# sb5a.net
KiCad netlist of a schematic drawn in EAGLE
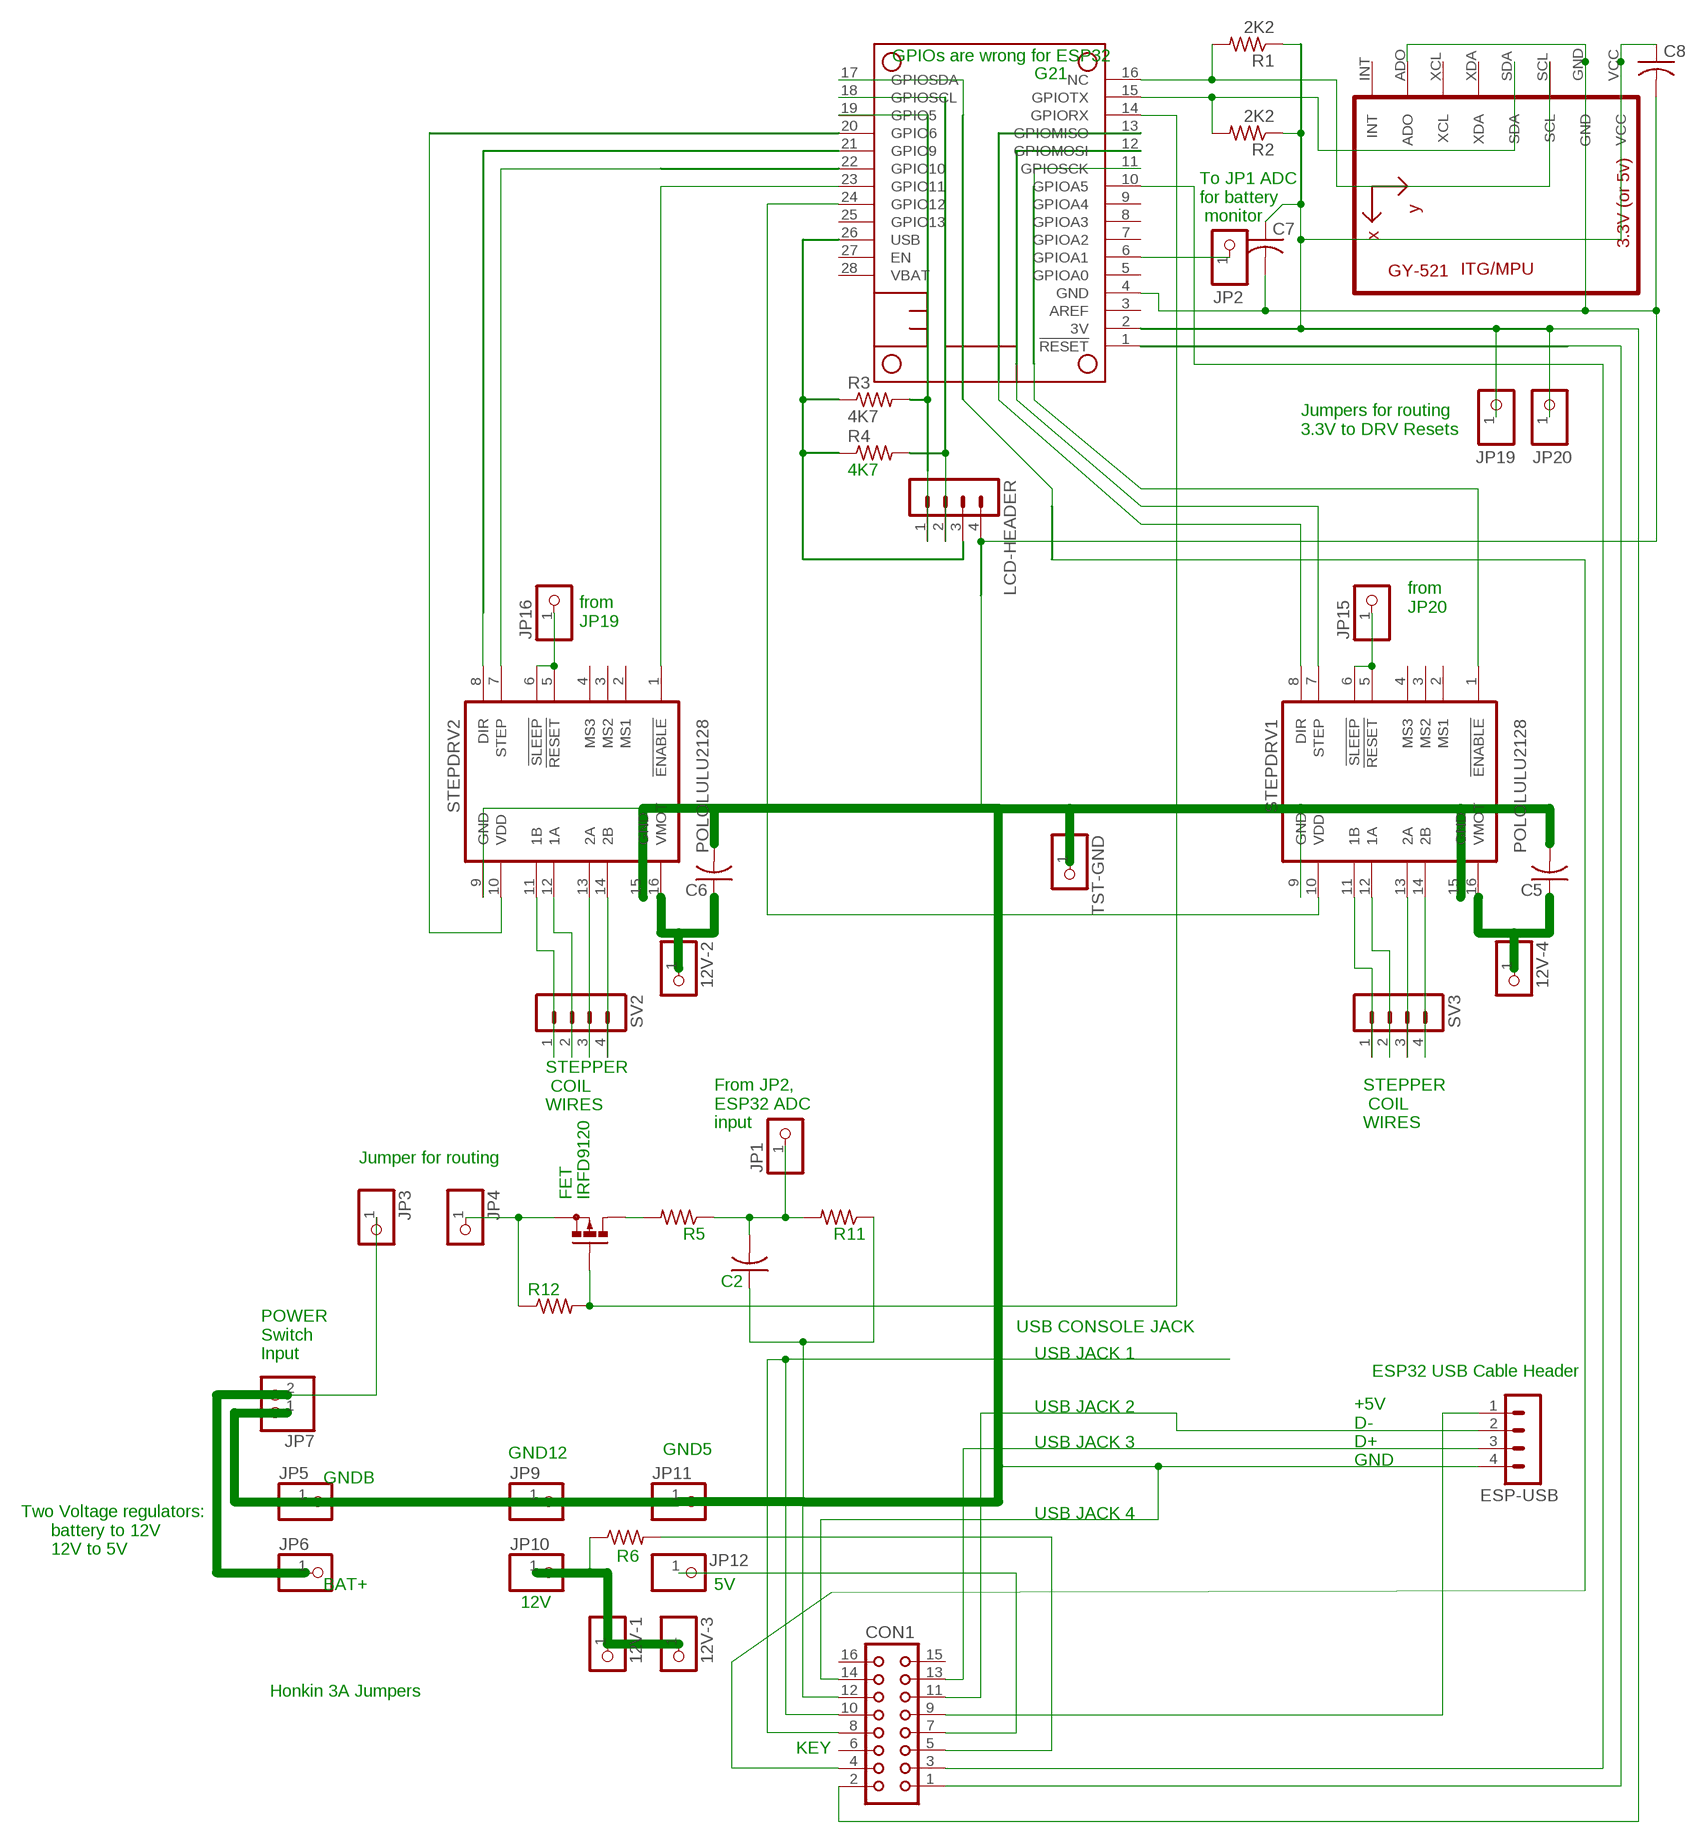
[diagram p0: schematic, sheet 1]

(export (version "E")
  (design (tool "Eeschema 10.0.6"))
  (components
    (comp (ref "12V-1")
      (value "PINHD-1X1")
      (footprint "eagle-import:1X01")
      (libsource (lib "eagle-import") (part "PINHD-1X1"))
    )
    (comp (ref "12V-2")
      (value "PINHD-1X1")
      (footprint "eagle-import:1X01")
      (libsource (lib "eagle-import") (part "PINHD-1X1"))
    )
    (comp (ref "12V-3")
      (value "PINHD-1X1")
      (footprint "eagle-import:1X01")
      (libsource (lib "eagle-import") (part "PINHD-1X1"))
    )
    (comp (ref "12V-4")
      (value "PINHD-1X1")
      (footprint "eagle-import:1X01")
      (libsource (lib "eagle-import") (part "PINHD-1X1"))
    )
    (comp (ref "C2")
      (value "C-US050-025X075")
      (footprint "eagle-import:C050-025X075")
      (libsource (lib "eagle-import") (part "C-US050-025X075"))
    )
    (comp (ref "C5")
      (value "C-US050-024X044")
      (footprint "eagle-import:C050-024X044")
      (libsource (lib "eagle-import") (part "C-US050-024X044"))
    )
    (comp (ref "C6")
      (value "C-US050-024X044")
      (footprint "eagle-import:C050-024X044")
      (libsource (lib "eagle-import") (part "C-US050-024X044"))
    )
    (comp (ref "C7")
      (value "C-US050-024X044")
      (footprint "eagle-import:C050-024X044")
      (libsource (lib "eagle-import") (part "C-US050-024X044"))
    )
    (comp (ref "C8")
      (value "C-US050-024X044")
      (footprint "eagle-import:C050-024X044")
      (libsource (lib "eagle-import") (part "C-US050-024X044"))
    )
    (comp (ref "CON1")
      (value "CON16")
      (footprint "eagle-import:CON16")
      (libsource (lib "eagle-import") (part "CON16"))
    )
    (comp (ref "ESP-USB")
      (value "MA04-1")
      (footprint "eagle-import:MA04-1")
      (libsource (lib "eagle-import") (part "MA04-1"))
    )
    (comp (ref "FET")
      (value "IRFD9120")
      (footprint "eagle-import:C370-01")
      (libsource (lib "eagle-import") (part "IRFD9120"))
    )
    (comp (ref "JP1")
      (value "PINHD-1X1")
      (footprint "eagle-import:1X01")
      (libsource (lib "eagle-import") (part "PINHD-1X1"))
    )
    (comp (ref "JP2")
      (value "PINHD-1X1")
      (footprint "eagle-import:1X01")
      (libsource (lib "eagle-import") (part "PINHD-1X1"))
    )
    (comp (ref "JP3")
      (value "PINHD-1X1")
      (footprint "eagle-import:1X01")
      (libsource (lib "eagle-import") (part "PINHD-1X1"))
    )
    (comp (ref "JP4")
      (value "PINHD-1X1")
      (footprint "eagle-import:1X01")
      (libsource (lib "eagle-import") (part "PINHD-1X1"))
    )
    (comp (ref "JP5")
      (value "PINHD-1X1")
      (footprint "eagle-import:1X01")
      (libsource (lib "eagle-import") (part "PINHD-1X1"))
    )
    (comp (ref "JP6")
      (value "PINHD-1X1")
      (footprint "eagle-import:1X01")
      (libsource (lib "eagle-import") (part "PINHD-1X1"))
    )
    (comp (ref "JP7")
      (value "PINHD-1X2")
      (footprint "eagle-import:1X02")
      (libsource (lib "eagle-import") (part "PINHD-1X2"))
    )
    (comp (ref "JP9")
      (value "PINHD-1X1")
      (footprint "eagle-import:1X01")
      (libsource (lib "eagle-import") (part "PINHD-1X1"))
    )
    (comp (ref "JP10")
      (value "PINHD-1X1")
      (footprint "eagle-import:1X01")
      (libsource (lib "eagle-import") (part "PINHD-1X1"))
    )
    (comp (ref "JP11")
      (value "PINHD-1X1")
      (footprint "eagle-import:1X01")
      (libsource (lib "eagle-import") (part "PINHD-1X1"))
    )
    (comp (ref "JP12")
      (value "PINHD-1X1")
      (footprint "eagle-import:1X01")
      (libsource (lib "eagle-import") (part "PINHD-1X1"))
    )
    (comp (ref "JP15")
      (value "PINHD-1X1")
      (footprint "eagle-import:1X01")
      (libsource (lib "eagle-import") (part "PINHD-1X1"))
    )
    (comp (ref "JP16")
      (value "PINHD-1X1")
      (footprint "eagle-import:1X01")
      (libsource (lib "eagle-import") (part "PINHD-1X1"))
    )
    (comp (ref "JP19")
      (value "PINHD-1X1")
      (footprint "eagle-import:1X01")
      (libsource (lib "eagle-import") (part "PINHD-1X1"))
    )
    (comp (ref "JP20")
      (value "PINHD-1X1")
      (footprint "eagle-import:1X01")
      (libsource (lib "eagle-import") (part "PINHD-1X1"))
    )
    (comp (ref "LCD-HEADER")
      (value "MA04-1")
      (footprint "eagle-import:MA04-1")
      (libsource (lib "eagle-import") (part "MA04-1"))
    )
    (comp (ref "MS2")
      (value "FEATHERWING_NOHOLES")
      (footprint "eagle-import:FEATHERWING_NOHOLES")
      (libsource (lib "eagle-import") (part "FEATHERWING_NOHOLES"))
    )
    (comp (ref "R1")
      (value "2K2")
      (footprint "eagle-import:0309_12")
      (libsource (lib "eagle-import") (part "resistor_348_R-US_0309/12"))
    )
    (comp (ref "R2")
      (value "2K2")
      (footprint "eagle-import:0309_12")
      (libsource (lib "eagle-import") (part "resistor_348_R-US_0309/12"))
    )
    (comp (ref "R3")
      (value "4K7")
      (footprint "eagle-import:0309_12")
      (libsource (lib "eagle-import") (part "resistor_348_R-US_0309/12"))
    )
    (comp (ref "R4")
      (value "4K7")
      (footprint "eagle-import:0309_12")
      (libsource (lib "eagle-import") (part "resistor_348_R-US_0309/12"))
    )
    (comp (ref "R5")
      (value "R-US_0207/10")
      (footprint "eagle-import:0207_10")
      (libsource (lib "eagle-import") (part "R-US_0207/10"))
    )
    (comp (ref "R6")
      (value "R-US_0207/10")
      (footprint "eagle-import:0207_10")
      (libsource (lib "eagle-import") (part "R-US_0207/10"))
    )
    (comp (ref "R11")
      (value "R-US_0207/10")
      (footprint "eagle-import:0207_10")
      (libsource (lib "eagle-import") (part "R-US_0207/10"))
    )
    (comp (ref "R12")
      (value "R-US_0207/10")
      (footprint "eagle-import:0207_10")
      (libsource (lib "eagle-import") (part "R-US_0207/10"))
    )
    (comp (ref "STEPDRV1")
      (value "POLOLULU2128")
      (footprint "eagle-import:POLOLULU2128")
      (libsource (lib "eagle-import") (part "POLOLULU2128"))
    )
    (comp (ref "STEPDRV2")
      (value "POLOLULU2128")
      (footprint "eagle-import:POLOLULU2128")
      (libsource (lib "eagle-import") (part "POLOLULU2128"))
    )
    (comp (ref "SV2")
      (value "MA04-1")
      (footprint "eagle-import:MA04-1")
      (libsource (lib "eagle-import") (part "MA04-1"))
    )
    (comp (ref "SV3")
      (value "MA04-1")
      (footprint "eagle-import:MA04-1")
      (libsource (lib "eagle-import") (part "MA04-1"))
    )
    (comp (ref "TST-GND")
      (value "PINHD-1X1")
      (footprint "eagle-import:1X01")
      (libsource (lib "eagle-import") (part "PINHD-1X1"))
    )
    (comp (ref "U1")
      (value "GY-521MPU6050")
      (footprint "eagle-import:GY-521")
      (libsource (lib "eagle-import") (part "GY-521MPU6050"))
    )
  )
  (nets
    (net (code "1") (name "/VBAT") (class "Default")
      (node (ref "MS2") (pin "28") (pinfunction "VBAT_28") (pintype "power_in"))
    )
    (net (code "2") (name "Net-(12V-1-Pad1)") (class "Default")
      (node (ref "12V-1") (pin "1") (pinfunction "1_1") (pintype "passive"))
      (node (ref "12V-3") (pin "1") (pinfunction "1_1") (pintype "passive"))
      (node (ref "JP10") (pin "1") (pinfunction "1_1") (pintype "passive"))
      (node (ref "R6") (pin "1") (pinfunction "1_1") (pintype "passive"))
    )
    (net (code "3") (name "Net-(C2-Pad2)") (class "Default")
      (node (ref "C2") (pin "2") (pinfunction "2_2") (pintype "passive"))
      (node (ref "JP1") (pin "1") (pinfunction "1_1") (pintype "passive"))
      (node (ref "R11") (pin "2") (pinfunction "2_2") (pintype "passive"))
      (node (ref "R5") (pin "1") (pinfunction "1_1") (pintype "passive"))
    )
    (net (code "4") (name "Net-(CON1-Pad5)") (class "Default")
      (node (ref "CON1") (pin "5") (pinfunction "5_5") (pintype "passive"))
      (node (ref "R6") (pin "2") (pinfunction "2_2") (pintype "passive"))
    )
    (net (code "5") (name "Net-(CON1-Pad7)") (class "Default")
      (node (ref "CON1") (pin "7") (pinfunction "7_7") (pintype "passive"))
      (node (ref "JP12") (pin "1") (pinfunction "1_1") (pintype "passive"))
    )
    (net (code "6") (name "Net-(CON1-Pad9)") (class "Default")
      (node (ref "CON1") (pin "9") (pinfunction "9_9") (pintype "passive"))
      (node (ref "ESP-USB") (pin "1") (pinfunction "1_1") (pintype "passive"))
    )
    (net (code "7") (name "Net-(CON1-Pad10)") (class "Default")
      (node (ref "CON1") (pin "10") (pinfunction "10_10") (pintype "passive"))
      (node (ref "CON1") (pin "8") (pinfunction "8_8") (pintype "passive"))
    )
    (net (code "8") (name "Net-(CON1-Pad11)") (class "Default")
      (node (ref "CON1") (pin "11") (pinfunction "11_11") (pintype "passive"))
      (node (ref "ESP-USB") (pin "2") (pinfunction "2_2") (pintype "passive"))
    )
    (net (code "9") (name "Net-(CON1-Pad13)") (class "Default")
      (node (ref "CON1") (pin "13") (pinfunction "13_13") (pintype "passive"))
      (node (ref "ESP-USB") (pin "3") (pinfunction "3_3") (pintype "passive"))
    )
    (net (code "10") (name "Net-(FET-D-PadD1)") (class "Default")
      (node (ref "FET") (pin "D") (pinfunction "D_D") (pintype "passive"))
      (node (ref "FET") (pin "D1") (pinfunction "D_D1") (pintype "passive"))
      (node (ref "R5") (pin "2") (pinfunction "2_2") (pintype "passive"))
    )
    (net (code "11") (name "Net-(FET-PadS)") (class "Default")
      (node (ref "FET") (pin "S") (pinfunction "S_S") (pintype "passive"))
      (node (ref "JP4") (pin "1") (pinfunction "1_1") (pintype "passive"))
      (node (ref "R12") (pin "1") (pinfunction "1_1") (pintype "passive"))
    )
    (net (code "12") (name "Net-(JP3-Pad1)") (class "Default")
      (node (ref "JP3") (pin "1") (pinfunction "1_1") (pintype "passive"))
      (node (ref "JP6") (pin "1") (pinfunction "1_1") (pintype "passive"))
      (node (ref "JP7") (pin "2") (pinfunction "2_2") (pintype "passive"))
    )
    (net (code "13") (name "Net-(MS2-3V)") (class "Default")
      (node (ref "C7") (pin "1") (pinfunction "1_1") (pintype "passive"))
      (node (ref "C8") (pin "1") (pinfunction "1_1") (pintype "passive"))
      (node (ref "CON1") (pin "2") (pinfunction "2_2") (pintype "passive"))
      (node (ref "JP19") (pin "1") (pinfunction "1_1") (pintype "passive"))
      (node (ref "JP20") (pin "1") (pinfunction "1_1") (pintype "passive"))
      (node (ref "MS2") (pin "2") (pinfunction "3V_2") (pintype "power_in"))
      (node (ref "R1") (pin "1") (pinfunction "1_1") (pintype "passive"))
      (node (ref "R2") (pin "1") (pinfunction "1_1") (pintype "passive"))
      (node (ref "U1") (pin "VCC") (pinfunction "VCC_VCC") (pintype "bidirectional"))
    )
    (net (code "14") (name "Net-(MS2-GND)") (class "Default")
      (node (ref "C2") (pin "1") (pinfunction "1_1") (pintype "passive"))
      (node (ref "C5") (pin "2") (pinfunction "2_2") (pintype "passive"))
      (node (ref "C6") (pin "2") (pinfunction "2_2") (pintype "passive"))
      (node (ref "C7") (pin "2") (pinfunction "2_2") (pintype "passive"))
      (node (ref "C8") (pin "2") (pinfunction "2_2") (pintype "passive"))
      (node (ref "CON1") (pin "12") (pinfunction "12_12") (pintype "passive"))
      (node (ref "CON1") (pin "14") (pinfunction "14_14") (pintype "passive"))
      (node (ref "ESP-USB") (pin "4") (pinfunction "4_4") (pintype "passive"))
      (node (ref "JP11") (pin "1") (pinfunction "1_1") (pintype "passive"))
      (node (ref "JP5") (pin "1") (pinfunction "1_1") (pintype "passive"))
      (node (ref "JP7") (pin "1") (pinfunction "1_1") (pintype "passive"))
      (node (ref "JP9") (pin "1") (pinfunction "1_1") (pintype "passive"))
      (node (ref "LCD-HEADER") (pin "4") (pinfunction "4_4") (pintype "passive"))
      (node (ref "MS2") (pin "4") (pinfunction "GND_4") (pintype "power_in"))
      (node (ref "R11") (pin "1") (pinfunction "1_1") (pintype "passive"))
      (node (ref "STEPDRV1") (pin "15") (pinfunction "GND_15") (pintype "power_in"))
      (node (ref "STEPDRV1") (pin "9") (pinfunction "GND_9") (pintype "power_in"))
      (node (ref "STEPDRV2") (pin "15") (pinfunction "GND_15") (pintype "power_in"))
      (node (ref "STEPDRV2") (pin "9") (pinfunction "GND_9") (pintype "power_in"))
      (node (ref "TST-GND") (pin "1") (pinfunction "1_1") (pintype "passive"))
      (node (ref "U1") (pin "ADO") (pinfunction "ADO_ADO") (pintype "bidirectional"))
      (node (ref "U1") (pin "GND") (pinfunction "GND_GND") (pintype "bidirectional"))
    )
    (net (code "15") (name "Net-(MS2-GPIO5)") (class "Default")
      (node (ref "LCD-HEADER") (pin "1") (pinfunction "1_1") (pintype "passive"))
      (node (ref "MS2") (pin "19") (pinfunction "GPIO5_19") (pintype "bidirectional"))
      (node (ref "R3") (pin "2") (pinfunction "2_2") (pintype "passive"))
    )
    (net (code "16") (name "Net-(MS2-GPIO6)") (class "Default")
      (node (ref "MS2") (pin "20") (pinfunction "GPIO6_20") (pintype "bidirectional"))
      (node (ref "STEPDRV2") (pin "10") (pinfunction "VDD_10") (pintype "power_in"))
    )
    (net (code "17") (name "Net-(MS2-GPIO9)") (class "Default")
      (node (ref "MS2") (pin "21") (pinfunction "GPIO9_21") (pintype "bidirectional"))
      (node (ref "STEPDRV2") (pin "8") (pinfunction "DIR_8") (pintype "input"))
    )
    (net (code "18") (name "Net-(MS2-GPIO10)") (class "Default")
      (node (ref "MS2") (pin "22") (pinfunction "GPIO10_22") (pintype "bidirectional"))
      (node (ref "STEPDRV2") (pin "7") (pinfunction "STEP_7") (pintype "input"))
    )
    (net (code "19") (name "Net-(MS2-GPIO11)") (class "Default")
      (node (ref "MS2") (pin "23") (pinfunction "GPIO11_23") (pintype "bidirectional"))
      (node (ref "STEPDRV2") (pin "1") (pinfunction "~{ENABLE}_1") (pintype "input"))
    )
    (net (code "20") (name "Net-(MS2-GPIO12)") (class "Default")
      (node (ref "MS2") (pin "24") (pinfunction "GPIO12_24") (pintype "bidirectional"))
      (node (ref "STEPDRV1") (pin "10") (pinfunction "VDD_10") (pintype "power_in"))
    )
    (net (code "21") (name "Net-(MS2-GPIOA1)") (class "Default")
      (node (ref "JP2") (pin "1") (pinfunction "1_1") (pintype "passive"))
      (node (ref "MS2") (pin "6") (pinfunction "GPIOA1_6") (pintype "bidirectional"))
    )
    (net (code "22") (name "Net-(MS2-GPIOA5)") (class "Default")
      (node (ref "CON1") (pin "3") (pinfunction "3_3") (pintype "passive"))
      (node (ref "MS2") (pin "10") (pinfunction "GPIOA5_10") (pintype "bidirectional"))
    )
    (net (code "23") (name "Net-(MS2-GPIOMISO)") (class "Default")
      (node (ref "MS2") (pin "13") (pinfunction "GPIOMISO_13") (pintype "bidirectional"))
      (node (ref "STEPDRV1") (pin "8") (pinfunction "DIR_8") (pintype "input"))
    )
    (net (code "24") (name "Net-(MS2-GPIOMOSI)") (class "Default")
      (node (ref "MS2") (pin "12") (pinfunction "GPIOMOSI_12") (pintype "bidirectional"))
      (node (ref "STEPDRV1") (pin "7") (pinfunction "STEP_7") (pintype "input"))
    )
    (net (code "25") (name "Net-(MS2-GPIORX)") (class "Default")
      (node (ref "FET") (pin "G") (pinfunction "G_G") (pintype "passive"))
      (node (ref "MS2") (pin "14") (pinfunction "GPIORX_14") (pintype "bidirectional"))
      (node (ref "R12") (pin "2") (pinfunction "2_2") (pintype "passive"))
    )
    (net (code "26") (name "Net-(MS2-GPIOSCK)") (class "Default")
      (node (ref "MS2") (pin "11") (pinfunction "GPIOSCK_11") (pintype "bidirectional"))
      (node (ref "STEPDRV1") (pin "1") (pinfunction "~{ENABLE}_1") (pintype "input"))
    )
    (net (code "27") (name "Net-(MS2-GPIOSCL)") (class "Default")
      (node (ref "LCD-HEADER") (pin "2") (pinfunction "2_2") (pintype "passive"))
      (node (ref "MS2") (pin "18") (pinfunction "GPIOSCL_18") (pintype "bidirectional"))
      (node (ref "R4") (pin "2") (pinfunction "2_2") (pintype "passive"))
    )
    (net (code "28") (name "Net-(MS2-GPIOSDA)") (class "Default")
      (node (ref "CON1") (pin "4") (pinfunction "4_4") (pintype "passive"))
      (node (ref "MS2") (pin "17") (pinfunction "GPIOSDA_17") (pintype "bidirectional"))
    )
    (net (code "29") (name "Net-(MS2-GPIOTX)") (class "Default")
      (node (ref "MS2") (pin "15") (pinfunction "GPIOTX_15") (pintype "bidirectional"))
      (node (ref "R2") (pin "2") (pinfunction "2_2") (pintype "passive"))
      (node (ref "U1") (pin "SDA") (pinfunction "SDA_SDA") (pintype "bidirectional"))
    )
    (net (code "30") (name "Net-(MS2-NC)") (class "Default")
      (node (ref "MS2") (pin "16") (pinfunction "NC_16") (pintype "passive"))
      (node (ref "R1") (pin "2") (pinfunction "2_2") (pintype "passive"))
      (node (ref "U1") (pin "SCL") (pinfunction "SCL_SCL") (pintype "bidirectional"))
    )
    (net (code "31") (name "Net-(MS2-USB)") (class "Default")
      (node (ref "LCD-HEADER") (pin "3") (pinfunction "3_3") (pintype "passive"))
      (node (ref "MS2") (pin "26") (pinfunction "USB_26") (pintype "power_in"))
      (node (ref "R3") (pin "1") (pinfunction "1_1") (pintype "passive"))
      (node (ref "R4") (pin "1") (pinfunction "1_1") (pintype "passive"))
    )
    (net (code "32") (name "Net-(MS2-~{RESET})") (class "Default")
      (node (ref "CON1") (pin "1") (pinfunction "1_1") (pintype "passive"))
      (node (ref "MS2") (pin "1") (pinfunction "~{RESET}_1") (pintype "input"))
    )
    (net (code "33") (name "Net-(STEPDRV1-1A)") (class "Default")
      (node (ref "STEPDRV1") (pin "12") (pinfunction "1A_12") (pintype "output"))
      (node (ref "SV3") (pin "2") (pinfunction "2_2") (pintype "passive"))
    )
    (net (code "34") (name "Net-(STEPDRV1-1B)") (class "Default")
      (node (ref "STEPDRV1") (pin "11") (pinfunction "1B_11") (pintype "output"))
      (node (ref "SV3") (pin "1") (pinfunction "1_1") (pintype "passive"))
    )
    (net (code "35") (name "Net-(STEPDRV1-2A)") (class "Default")
      (node (ref "STEPDRV1") (pin "13") (pinfunction "2A_13") (pintype "output"))
      (node (ref "SV3") (pin "3") (pinfunction "3_3") (pintype "passive"))
    )
    (net (code "36") (name "Net-(STEPDRV1-2B)") (class "Default")
      (node (ref "STEPDRV1") (pin "14") (pinfunction "2B_14") (pintype "output"))
      (node (ref "SV3") (pin "4") (pinfunction "4_4") (pintype "passive"))
    )
    (net (code "37") (name "Net-(STEPDRV1-VMOT)") (class "Default")
      (node (ref "12V-4") (pin "1") (pinfunction "1_1") (pintype "passive"))
      (node (ref "C5") (pin "1") (pinfunction "1_1") (pintype "passive"))
      (node (ref "STEPDRV1") (pin "16") (pinfunction "VMOT_16") (pintype "power_in"))
    )
    (net (code "38") (name "Net-(STEPDRV1-~{RESET})") (class "Default")
      (node (ref "JP15") (pin "1") (pinfunction "1_1") (pintype "passive"))
      (node (ref "STEPDRV1") (pin "5") (pinfunction "~{RESET}_5") (pintype "input"))
      (node (ref "STEPDRV1") (pin "6") (pinfunction "~{SLEEP}_6") (pintype "input"))
    )
    (net (code "39") (name "Net-(STEPDRV2-1A)") (class "Default")
      (node (ref "STEPDRV2") (pin "12") (pinfunction "1A_12") (pintype "output"))
      (node (ref "SV2") (pin "2") (pinfunction "2_2") (pintype "passive"))
    )
    (net (code "40") (name "Net-(STEPDRV2-1B)") (class "Default")
      (node (ref "STEPDRV2") (pin "11") (pinfunction "1B_11") (pintype "output"))
      (node (ref "SV2") (pin "1") (pinfunction "1_1") (pintype "passive"))
    )
    (net (code "41") (name "Net-(STEPDRV2-2A)") (class "Default")
      (node (ref "STEPDRV2") (pin "13") (pinfunction "2A_13") (pintype "output"))
      (node (ref "SV2") (pin "3") (pinfunction "3_3") (pintype "passive"))
    )
    (net (code "42") (name "Net-(STEPDRV2-2B)") (class "Default")
      (node (ref "STEPDRV2") (pin "14") (pinfunction "2B_14") (pintype "output"))
      (node (ref "SV2") (pin "4") (pinfunction "4_4") (pintype "passive"))
    )
    (net (code "43") (name "Net-(STEPDRV2-VMOT)") (class "Default")
      (node (ref "12V-2") (pin "1") (pinfunction "1_1") (pintype "passive"))
      (node (ref "C6") (pin "1") (pinfunction "1_1") (pintype "passive"))
      (node (ref "STEPDRV2") (pin "16") (pinfunction "VMOT_16") (pintype "power_in"))
    )
    (net (code "44") (name "Net-(STEPDRV2-~{RESET})") (class "Default")
      (node (ref "JP16") (pin "1") (pinfunction "1_1") (pintype "passive"))
      (node (ref "STEPDRV2") (pin "5") (pinfunction "~{RESET}_5") (pintype "input"))
      (node (ref "STEPDRV2") (pin "6") (pinfunction "~{SLEEP}_6") (pintype "input"))
    )
    (net (code "45") (name "unconnected-(CON1-Pad6)") (class "Default")
      (node (ref "CON1") (pin "6") (pinfunction "6_6") (pintype "passive"))
    )
    (net (code "46") (name "unconnected-(CON1-Pad15)") (class "Default")
      (node (ref "CON1") (pin "15") (pinfunction "15_15") (pintype "passive"))
    )
    (net (code "47") (name "unconnected-(CON1-Pad16)") (class "Default")
      (node (ref "CON1") (pin "16") (pinfunction "16_16") (pintype "passive"))
    )
    (net (code "48") (name "unconnected-(MS2-AREF-Pad3)") (class "Default")
      (node (ref "MS2") (pin "3") (pinfunction "AREF_3") (pintype "passive"))
    )
    (net (code "49") (name "unconnected-(MS2-EN-Pad27)") (class "Default")
      (node (ref "MS2") (pin "27") (pinfunction "EN_27") (pintype "passive"))
    )
    (net (code "50") (name "unconnected-(MS2-GPIO13-Pad25)") (class "Default")
      (node (ref "MS2") (pin "25") (pinfunction "GPIO13_25") (pintype "bidirectional"))
    )
    (net (code "51") (name "unconnected-(MS2-GPIOA0-Pad5)") (class "Default")
      (node (ref "MS2") (pin "5") (pinfunction "GPIOA0_5") (pintype "bidirectional"))
    )
    (net (code "52") (name "unconnected-(MS2-GPIOA2-Pad7)") (class "Default")
      (node (ref "MS2") (pin "7") (pinfunction "GPIOA2_7") (pintype "bidirectional"))
    )
    (net (code "53") (name "unconnected-(MS2-GPIOA3-Pad8)") (class "Default")
      (node (ref "MS2") (pin "8") (pinfunction "GPIOA3_8") (pintype "bidirectional"))
    )
    (net (code "54") (name "unconnected-(MS2-GPIOA4-Pad9)") (class "Default")
      (node (ref "MS2") (pin "9") (pinfunction "GPIOA4_9") (pintype "bidirectional"))
    )
    (net (code "55") (name "unconnected-(STEPDRV1-MS1-Pad2)") (class "Default")
      (node (ref "STEPDRV1") (pin "2") (pinfunction "MS1_2") (pintype "input"))
    )
    (net (code "56") (name "unconnected-(STEPDRV1-MS2-Pad3)") (class "Default")
      (node (ref "STEPDRV1") (pin "3") (pinfunction "MS2_3") (pintype "input"))
    )
    (net (code "57") (name "unconnected-(STEPDRV1-MS3-Pad4)") (class "Default")
      (node (ref "STEPDRV1") (pin "4") (pinfunction "MS3_4") (pintype "input"))
    )
    (net (code "58") (name "unconnected-(STEPDRV2-MS1-Pad2)") (class "Default")
      (node (ref "STEPDRV2") (pin "2") (pinfunction "MS1_2") (pintype "input"))
    )
    (net (code "59") (name "unconnected-(STEPDRV2-MS2-Pad3)") (class "Default")
      (node (ref "STEPDRV2") (pin "3") (pinfunction "MS2_3") (pintype "input"))
    )
    (net (code "60") (name "unconnected-(STEPDRV2-MS3-Pad4)") (class "Default")
      (node (ref "STEPDRV2") (pin "4") (pinfunction "MS3_4") (pintype "input"))
    )
    (net (code "61") (name "unconnected-(U1-PadINT)") (class "Default")
      (node (ref "U1") (pin "INT") (pinfunction "INT_INT") (pintype "bidirectional"))
    )
    (net (code "62") (name "unconnected-(U1-PadXCL)") (class "Default")
      (node (ref "U1") (pin "XCL") (pinfunction "XCL_XCL") (pintype "bidirectional"))
    )
    (net (code "63") (name "unconnected-(U1-PadXDA)") (class "Default")
      (node (ref "U1") (pin "XDA") (pinfunction "XDA_XDA") (pintype "bidirectional"))
    )
  )
)
